# SensorRadiacion.net
KiCad netlist of a schematic drawn in Altium Designer
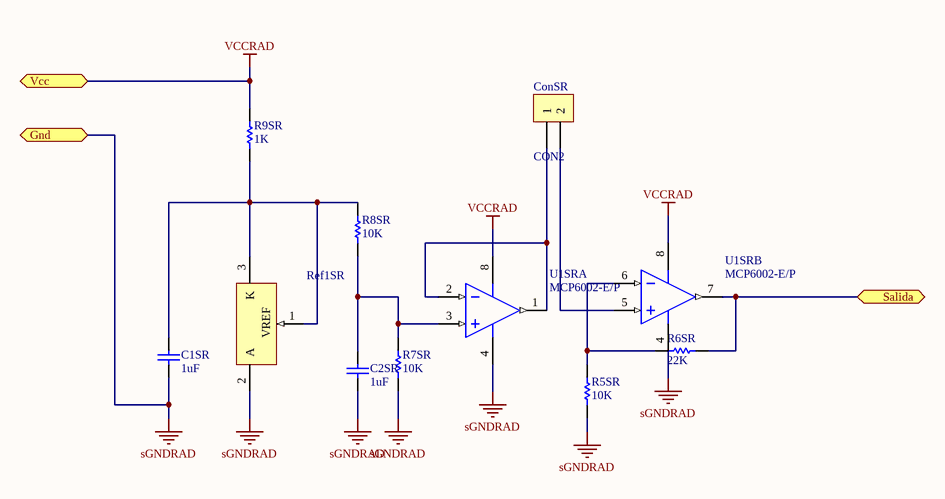
[diagram p0: SensorRadiacion.SchDoc]

(export (version "E")
  (design (tool "Eeschema 10.0.6"))
  (components
    (comp (ref "C1SR")
      (value "1uF")
      (footprint "CAPPOL100")
      (description "Capacitor")
      (libsource (lib "IDTILab") (part "CAP"))
    )
    (comp (ref "C2SR")
      (value "1uF")
      (footprint "CAPPOL100")
      (description "Capacitor")
      (libsource (lib "IDTILab") (part "CAP"))
    )
    (comp (ref "ConSR")
      (value "CON2")
      (footprint "BORNERA2 - T")
      (description "Conector 2")
      (libsource (lib "IDTILab") (part "CON2"))
    )
    (comp (ref "R5SR")
      (value "10K")
      (footprint "RES300")
      (description "Resistencia")
      (libsource (lib "IDTILab") (part "RES"))
    )
    (comp (ref "R6SR")
      (value "22K")
      (footprint "RES300")
      (description "Resistencia")
      (libsource (lib "IDTILab") (part "RES"))
    )
    (comp (ref "R7SR")
      (value "10K")
      (footprint "RES300")
      (description "Resistencia")
      (libsource (lib "IDTILab") (part "RES"))
    )
    (comp (ref "R8SR")
      (value "10K")
      (footprint "RES300")
      (description "Resistencia")
      (libsource (lib "IDTILab") (part "RES"))
    )
    (comp (ref "R9SR")
      (value "1K")
      (footprint "RES300")
      (description "Resistencia")
      (libsource (lib "IDTILab") (part "RES"))
    )
    (comp (ref "Ref1SR")
      (value "TL431ACLP")
      (footprint "LP03")
      (description "Adjustable Precision Shunt Regulator")
      (fields (field (name "PUBLISHER") "Altium Limited"))
      (libsource (lib "TI Power Mgt Voltage Regulator") (part "TL431ACLP"))
    )
    (comp (ref "U1SR")
      (value "MCP6002-E/P")
      (footprint "DIP8B")
      (description "1 MHz, Low-Power Operational Amplifier, 8-Pin PDIP, Extended Temperature")
      (fields (field (name "PUBLISHER") "Altium Limited"))
      (libsource (lib "Microchip Linear Devices") (part "MCP6002-E/P"))
    )
  )
  (nets
    (net (code "1") (name "/Salida") (class "Default")
      (node (ref "R6SR") (pin "1") (pinfunction "1_1") (pintype "passive"))
      (node (ref "U1SR") (pin "7") (pinfunction "VOUTB_7") (pintype "output"))
    )
    (net (code "2") (name "Net-(Ref1SR-K)") (class "Default")
      (node (ref "C1SR") (pin "2") (pinfunction "2_2") (pintype "passive"))
      (node (ref "R8SR") (pin "2") (pinfunction "2_2") (pintype "passive"))
      (node (ref "R9SR") (pin "1") (pinfunction "1_1") (pintype "passive"))
      (node (ref "Ref1SR") (pin "1") (pinfunction "VREF_1") (pintype "input"))
      (node (ref "Ref1SR") (pin "3") (pinfunction "K_3") (pintype "power_in"))
    )
    (net (code "3") (name "Net-(U1SRA-VINA+)") (class "Default")
      (node (ref "C2SR") (pin "2") (pinfunction "2_2") (pintype "passive"))
      (node (ref "R7SR") (pin "2") (pinfunction "2_2") (pintype "passive"))
      (node (ref "R8SR") (pin "1") (pinfunction "1_1") (pintype "passive"))
      (node (ref "U1SR") (pin "3") (pinfunction "VINA+_3") (pintype "input"))
    )
    (net (code "4") (name "Net-(U1SRA-VINA-)") (class "Default")
      (node (ref "ConSR") (pin "1") (pinfunction "1_1") (pintype "passive"))
      (node (ref "U1SR") (pin "1") (pinfunction "VOUTA_1") (pintype "output"))
      (node (ref "U1SR") (pin "2") (pinfunction "VINA-_2") (pintype "input"))
    )
    (net (code "5") (name "Net-(U1SRB-VINB+)") (class "Default")
      (node (ref "ConSR") (pin "2") (pinfunction "2_2") (pintype "passive"))
      (node (ref "U1SR") (pin "5") (pinfunction "VINB+_5") (pintype "input"))
    )
    (net (code "6") (name "Net-(U1SRB-VINB-)") (class "Default")
      (node (ref "R5SR") (pin "2") (pinfunction "2_2") (pintype "passive"))
      (node (ref "R6SR") (pin "2") (pinfunction "2_2") (pintype "passive"))
      (node (ref "U1SR") (pin "6") (pinfunction "VINB-_6") (pintype "input"))
    )
    (net (code "7") (name "VCCRAD") (class "Default")
      (node (ref "R9SR") (pin "2") (pinfunction "2_2") (pintype "passive"))
      (node (ref "U1SR") (pin "8") (pinfunction "VDD_8") (pintype "power_in"))
    )
    (net (code "8") (name "sGNDRAD") (class "Default")
      (node (ref "C1SR") (pin "1") (pinfunction "1_1") (pintype "passive"))
      (node (ref "C2SR") (pin "1") (pinfunction "1_1") (pintype "passive"))
      (node (ref "R5SR") (pin "1") (pinfunction "1_1") (pintype "passive"))
      (node (ref "R7SR") (pin "1") (pinfunction "1_1") (pintype "passive"))
      (node (ref "Ref1SR") (pin "2") (pinfunction "A_2") (pintype "power_in"))
      (node (ref "U1SR") (pin "4") (pinfunction "VSS_4") (pintype "power_in"))
    )
  )
)
